# Recepteur.net
KiCad netlist of a schematic drawn in Altium Designer
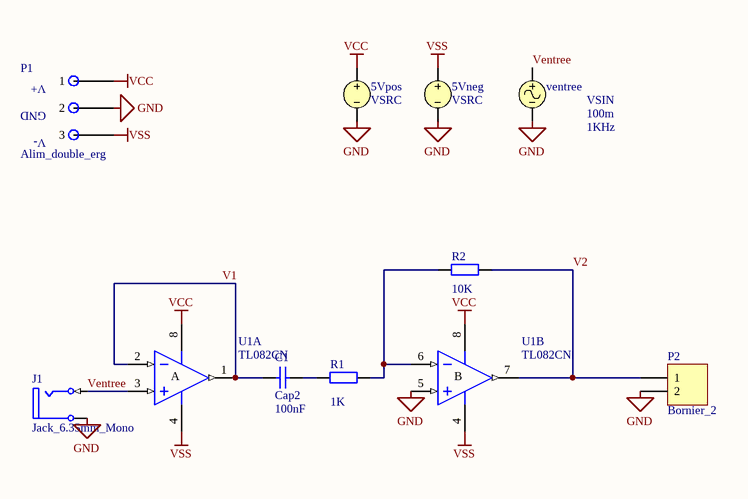
[diagram p0: Recepteur.SchDoc]

(export (version "E")
  (design (tool "Eeschema 10.0.6"))
  (components
    (comp (ref "5Vneg")
      (value "VSRC")
      (description "Voltage Source")
      (fields (field (name "PUBLISHER") "Altium Limited"))
      (libsource (lib "Simulation Sources") (part "VSRC"))
    )
    (comp (ref "5Vpos")
      (value "VSRC")
      (description "Voltage Source")
      (fields (field (name "PUBLISHER") "Altium Limited"))
      (libsource (lib "Simulation Sources") (part "VSRC"))
    )
    (comp (ref "C1")
      (value "Cap2")
      (footprint "CAPA2")
      (description "Capacitor")
      (fields (field (name "ALTIUM_VALUE") "100nF") (field (name "PUBLISHER") "Altium Limited"))
      (libsource (lib "LIBRAIRIE_INTEGREE_PHELMA1") (part "Cap2"))
    )
    (comp (ref "J1")
      (value "Jack_6.35mm_Mono")
      (footprint "Jack_6.5mm")
      (description "Jack Socket, 1/4\" [6.5mm], Thru-Hole, Vertical, 2-Conductor Open Circuit")
      (fields (field (name "PUBLISHER") "Altium Limited"))
      (libsource (lib "INTEGRATED_LIBRARY1_CONNECTEURS") (part "Jack_6.35mm_Mono"))
    )
    (comp (ref "P1")
      (value "Alim_double_erg")
      (footprint "Alim_double_erg")
      (description "3-Pin")
      (fields (field (name "PUBLISHER") "Altium Limited"))
      (libsource (lib "INTEGRATED_LIBRARY1_CONNECTEURS") (part "Alim_double_erg"))
    )
    (comp (ref "P2")
      (value "Bornier_2")
      (footprint "Bornier_2")
      (description "Header, 2-Pin")
      (fields (field (name "PUBLISHER") "Altium Limited"))
      (libsource (lib "INTEGRATED_LIBRARY1_CONNECTEURS") (part "Bornier_2"))
    )
    (comp (ref "R1")
      (value "1K")
      (footprint "res5_1/4W")
      (description "Resistor")
      (fields (field (name "Comment") "Res2") (field (name "PUBLISHER") "Altium Limited"))
      (libsource (lib "LIBRAIRIE_INTEGREE_PHELMA1") (part "Res2"))
    )
    (comp (ref "R2")
      (value "10K")
      (footprint "res5_1/4W")
      (description "Resistor")
      (fields (field (name "Comment") "Res2") (field (name "PUBLISHER") "Altium Limited"))
      (libsource (lib "LIBRAIRIE_INTEGREE_PHELMA1") (part "Res2"))
    )
    (comp (ref "U1")
      (value "TL082CN")
      (footprint "DIP8")
      (description "General-Purpose J-FET Dual Operational Amplifier")
      (fields (field (name "PUBLISHER") "Altium Limited"))
      (libsource (lib "LIBRAIRIE_INTEGREE_PHELMA1") (part "TL082CN"))
    )
    (comp (ref "ventree")
      (value "VSIN")
      (description "Sinusoidal Voltage Source")
      (fields
        (field (name "AMPLITUDE") "100m")
        (field (name "FREQUENCY") "1KHz")
        (field (name "PUBLISHER") "Altium Limited")
      )
      (libsource (lib "Simulation Sources") (part "VSIN"))
    )
  )
  (nets
    (net (code "1") (name "/V1") (class "Default")
      (node (ref "C1") (pin "1") (pinfunction "1_1") (pintype "passive"))
      (node (ref "U1") (pin "1") (pinfunction "OUT_1") (pintype "output"))
      (node (ref "U1") (pin "2") (pinfunction "IN-_2") (pintype "input"))
    )
    (net (code "2") (name "/V2") (class "Default")
      (node (ref "P2") (pin "1") (pinfunction "1_1") (pintype "passive"))
      (node (ref "R2") (pin "2") (pinfunction "2_2") (pintype "passive"))
      (node (ref "U1") (pin "7") (pinfunction "OUT_7") (pintype "output"))
    )
    (net (code "3") (name "/Ventree") (class "Default")
      (node (ref "J1") (pin "1") (pinfunction "T_1") (pintype "input"))
      (node (ref "U1") (pin "3") (pinfunction "IN+_3") (pintype "input"))
      (node (ref "ventree") (pin "1") (pinfunction "1_1") (pintype "passive"))
    )
    (net (code "4") (name "GND") (class "Default")
      (node (ref "5Vneg") (pin "2") (pinfunction "2_2") (pintype "passive"))
      (node (ref "5Vpos") (pin "2") (pinfunction "2_2") (pintype "passive"))
      (node (ref "J1") (pin "2") (pinfunction "S_2") (pintype "power_in"))
      (node (ref "P1") (pin "2") (pinfunction "2_2") (pintype "passive"))
      (node (ref "P2") (pin "2") (pinfunction "2_2") (pintype "passive"))
      (node (ref "U1") (pin "5") (pinfunction "IN+_5") (pintype "input"))
      (node (ref "ventree") (pin "2") (pinfunction "2_2") (pintype "passive"))
    )
    (net (code "5") (name "Net-(C1-Pad2)") (class "Default")
      (node (ref "C1") (pin "2") (pinfunction "2_2") (pintype "passive"))
      (node (ref "R1") (pin "1") (pinfunction "1_1") (pintype "passive"))
    )
    (net (code "6") (name "Net-(U1B-IN-)") (class "Default")
      (node (ref "R1") (pin "2") (pinfunction "2_2") (pintype "passive"))
      (node (ref "R2") (pin "1") (pinfunction "1_1") (pintype "passive"))
      (node (ref "U1") (pin "6") (pinfunction "IN-_6") (pintype "input"))
    )
    (net (code "7") (name "VCC") (class "Default")
      (node (ref "5Vpos") (pin "1") (pinfunction "1_1") (pintype "passive"))
      (node (ref "P1") (pin "1") (pinfunction "1_1") (pintype "passive"))
      (node (ref "U1") (pin "8") (pinfunction "V+_8") (pintype "power_in"))
    )
    (net (code "8") (name "VSS") (class "Default")
      (node (ref "5Vneg") (pin "1") (pinfunction "1_1") (pintype "passive"))
      (node (ref "P1") (pin "3") (pinfunction "3_3") (pintype "passive"))
      (node (ref "U1") (pin "4") (pinfunction "V-_4") (pintype "power_in"))
    )
  )
)
